# brick_serial_ble.net
KiCad netlist of a schematic drawn in EAGLE
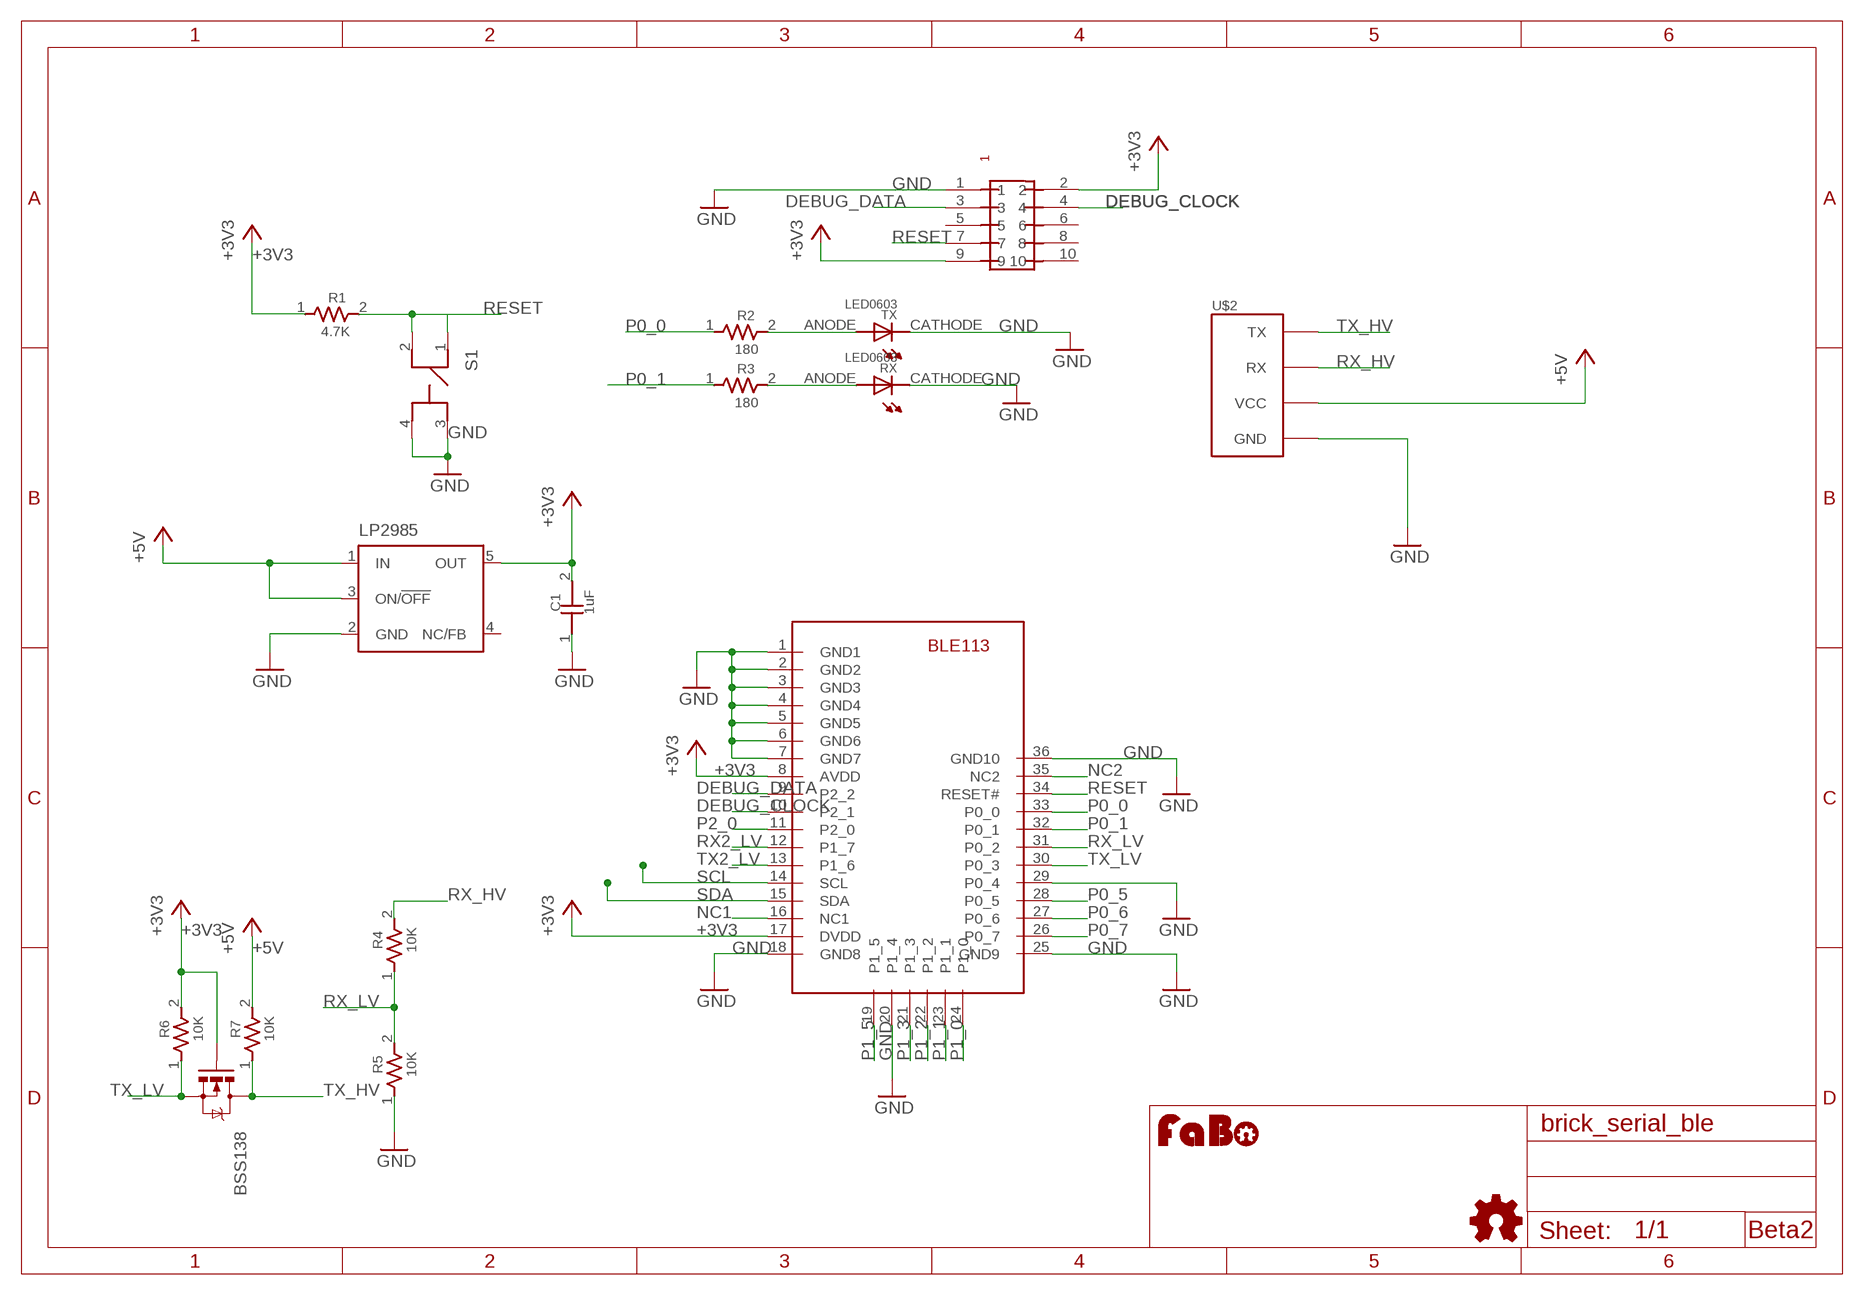
[diagram p0: schematic, sheet 1]

(export (version "E")
  (design (tool "Eeschema 10.0.6"))
  (components
    (comp (ref "BSS138")
      (value "MOSFET-NCHANNELSMD")
      (footprint "eagle-import:SOT23-3")
      (libsource (lib "eagle-import") (part "MOSFET-NCHANNELSMD"))
    )
    (comp (ref "C1")
      (value "1uF")
      (footprint "eagle-import:0603")
      (libsource (lib "eagle-import") (part "CAPACITOR0603"))
    )
    (comp (ref "LP2985")
      (value "LP2985-XXDBVR33")
      (footprint "eagle-import:SOT23-DBV")
      (libsource (lib "eagle-import") (part "LP2985-XXDBVR33"))
    )
    (comp (ref "R1")
      (value "4.7K")
      (footprint "eagle-import:0603")
      (libsource (lib "eagle-import") (part "RESISTOR0603"))
    )
    (comp (ref "R2")
      (value "180")
      (footprint "eagle-import:0603")
      (libsource (lib "eagle-import") (part "RESISTOR0603"))
    )
    (comp (ref "R3")
      (value "180")
      (footprint "eagle-import:0603")
      (libsource (lib "eagle-import") (part "RESISTOR0603"))
    )
    (comp (ref "R4")
      (value "10K")
      (footprint "eagle-import:0603")
      (libsource (lib "eagle-import") (part "RESISTOR0603"))
    )
    (comp (ref "R5")
      (value "10K")
      (footprint "eagle-import:0603")
      (libsource (lib "eagle-import") (part "RESISTOR0603"))
    )
    (comp (ref "R6")
      (value "10K")
      (footprint "eagle-import:0603")
      (libsource (lib "eagle-import") (part "RESISTOR0603"))
    )
    (comp (ref "R7")
      (value "10K")
      (footprint "eagle-import:0603")
      (libsource (lib "eagle-import") (part "RESISTOR0603"))
    )
    (comp (ref "RX")
      (value "LED0603")
      (footprint "eagle-import:0603")
      (libsource (lib "eagle-import") (part "LED0603"))
    )
    (comp (ref "S1")
      (value "SWITCH-LS6J2M-T")
      (footprint "eagle-import:SWITCH-LS6J2M-T")
      (libsource (lib "eagle-import") (part "SWITCH-LS6J2M-T"))
    )
    (comp (ref "TX")
      (value "LED0603")
      (footprint "eagle-import:0603")
      (libsource (lib "eagle-import") (part "LED0603"))
    )
    (comp (ref "U$1")
      (value "PIN-HEADER-SMT(1.27MM)2X5")
      (footprint "eagle-import:PIN-HEADER-SMT(1.27MM)2X5")
      (libsource (lib "eagle-import") (part "PIN-HEADER-SMT(1.27MM)2X5"))
    )
    (comp (ref "U$2")
      (value "BRICK_SERIAL")
      (footprint "eagle-import:BRICK_SERIAL")
      (libsource (lib "eagle-import") (part "BRICK_SERIAL"))
    )
    (comp (ref "U$3")
      (value "LOGO_FABO-S")
      (footprint "eagle-import:LOGO_FABO_S")
      (libsource (lib "eagle-import") (part "LOGO_FABO-S"))
    )
    (comp (ref "U$4")
      (value "LOGO_OSHW-S")
      (footprint "eagle-import:LOGO_OSHW_S")
      (libsource (lib "eagle-import") (part "LOGO_OSHW-S"))
    )
    (comp (ref "U$6")
      (value "BLUEGIGA-BLE113")
      (footprint "eagle-import:BLUEGIGA-BLE113")
      (libsource (lib "eagle-import") (part "BLUEGIGA-BLE113"))
    )
  )
  (nets
    (net (code "1") (name "+3V3") (class "Default")
      (node (ref "BSS138") (pin "1") (pinfunction "G_1") (pintype "passive"))
      (node (ref "C1") (pin "2") (pinfunction "2_2") (pintype "passive"))
      (node (ref "LP2985") (pin "5") (pinfunction "OUT_5") (pintype "passive"))
      (node (ref "R1") (pin "1") (pinfunction "1_1") (pintype "passive"))
      (node (ref "R6") (pin "2") (pinfunction "2_2") (pintype "passive"))
      (node (ref "U$1") (pin "2") (pinfunction "2_2") (pintype "bidirectional"))
      (node (ref "U$1") (pin "9") (pinfunction "9_9") (pintype "bidirectional"))
      (node (ref "U$6") (pin "17") (pinfunction "DVDD_17") (pintype "bidirectional"))
      (node (ref "U$6") (pin "8") (pinfunction "AVDD_8") (pintype "bidirectional"))
    )
    (net (code "2") (name "+5V") (class "Default")
      (node (ref "LP2985") (pin "1") (pinfunction "IN_1") (pintype "input"))
      (node (ref "LP2985") (pin "3") (pinfunction "ON/~{OFF}_3") (pintype "input"))
      (node (ref "R7") (pin "2") (pinfunction "2_2") (pintype "passive"))
      (node (ref "U$2") (pin "VCC") (pinfunction "VCC_VCC") (pintype "bidirectional"))
    )
    (net (code "3") (name "/DEBUG_CLOCK") (class "Default")
      (node (ref "U$1") (pin "4") (pinfunction "4_4") (pintype "bidirectional"))
      (node (ref "U$6") (pin "10") (pinfunction "P2_1_10") (pintype "bidirectional"))
    )
    (net (code "4") (name "/DEBUG_DATA") (class "Default")
      (node (ref "U$1") (pin "3") (pinfunction "3_3") (pintype "bidirectional"))
      (node (ref "U$6") (pin "9") (pinfunction "P2_2_9") (pintype "bidirectional"))
    )
    (net (code "5") (name "/NC1") (class "Default")
      (node (ref "U$6") (pin "16") (pinfunction "NC1_16") (pintype "bidirectional"))
    )
    (net (code "6") (name "/NC2") (class "Default")
      (node (ref "U$6") (pin "35") (pinfunction "NC2_35") (pintype "bidirectional"))
    )
    (net (code "7") (name "/P0_0") (class "Default")
      (node (ref "R2") (pin "1") (pinfunction "1_1") (pintype "passive"))
      (node (ref "U$6") (pin "33") (pinfunction "P0_0_33") (pintype "bidirectional"))
    )
    (net (code "8") (name "/P0_1") (class "Default")
      (node (ref "R3") (pin "1") (pinfunction "1_1") (pintype "passive"))
      (node (ref "U$6") (pin "32") (pinfunction "P0_1_32") (pintype "bidirectional"))
    )
    (net (code "9") (name "/P0_5") (class "Default")
      (node (ref "U$6") (pin "28") (pinfunction "P0_5_28") (pintype "bidirectional"))
    )
    (net (code "10") (name "/P0_6") (class "Default")
      (node (ref "U$6") (pin "27") (pinfunction "P0_6_27") (pintype "bidirectional"))
    )
    (net (code "11") (name "/P0_7") (class "Default")
      (node (ref "U$6") (pin "26") (pinfunction "P0_7_26") (pintype "bidirectional"))
    )
    (net (code "12") (name "/P1_0") (class "Default")
      (node (ref "U$6") (pin "24") (pinfunction "P1_0_24") (pintype "bidirectional"))
    )
    (net (code "13") (name "/P1_1") (class "Default")
      (node (ref "U$6") (pin "23") (pinfunction "P1_1_23") (pintype "bidirectional"))
    )
    (net (code "14") (name "/P1_2") (class "Default")
      (node (ref "U$6") (pin "22") (pinfunction "P1_2_22") (pintype "bidirectional"))
    )
    (net (code "15") (name "/P1_3") (class "Default")
      (node (ref "U$6") (pin "21") (pinfunction "P1_3_21") (pintype "bidirectional"))
    )
    (net (code "16") (name "/P1_5") (class "Default")
      (node (ref "U$6") (pin "19") (pinfunction "P1_5_19") (pintype "bidirectional"))
    )
    (net (code "17") (name "/P2_0") (class "Default")
      (node (ref "U$6") (pin "11") (pinfunction "P2_0_11") (pintype "bidirectional"))
    )
    (net (code "18") (name "/RESET") (class "Default")
      (node (ref "R1") (pin "2") (pinfunction "2_2") (pintype "passive"))
      (node (ref "S1") (pin "1") (pinfunction "1_1") (pintype "bidirectional"))
      (node (ref "S1") (pin "2") (pinfunction "2_2") (pintype "bidirectional"))
      (node (ref "U$1") (pin "7") (pinfunction "7_7") (pintype "bidirectional"))
      (node (ref "U$6") (pin "34") (pinfunction "RESET#_34") (pintype "bidirectional"))
    )
    (net (code "19") (name "/RX2_LV") (class "Default")
      (node (ref "U$6") (pin "12") (pinfunction "P1_7_12") (pintype "bidirectional"))
    )
    (net (code "20") (name "/RX_HV") (class "Default")
      (node (ref "R4") (pin "2") (pinfunction "2_2") (pintype "passive"))
      (node (ref "U$2") (pin "RX") (pinfunction "RX_RX") (pintype "bidirectional"))
    )
    (net (code "21") (name "/RX_LV") (class "Default")
      (node (ref "R4") (pin "1") (pinfunction "1_1") (pintype "passive"))
      (node (ref "R5") (pin "2") (pinfunction "2_2") (pintype "passive"))
      (node (ref "U$6") (pin "31") (pinfunction "P0_2_31") (pintype "bidirectional"))
    )
    (net (code "22") (name "/SCL") (class "Default")
      (node (ref "U$6") (pin "14") (pinfunction "SCL_14") (pintype "bidirectional"))
    )
    (net (code "23") (name "/SDA") (class "Default")
      (node (ref "U$6") (pin "15") (pinfunction "SDA_15") (pintype "bidirectional"))
    )
    (net (code "24") (name "/TX2_LV") (class "Default")
      (node (ref "U$6") (pin "13") (pinfunction "P1_6_13") (pintype "bidirectional"))
    )
    (net (code "25") (name "/TX_HV") (class "Default")
      (node (ref "BSS138") (pin "3") (pinfunction "D_3") (pintype "passive"))
      (node (ref "R7") (pin "1") (pinfunction "1_1") (pintype "passive"))
      (node (ref "U$2") (pin "TX") (pinfunction "TX_TX") (pintype "bidirectional"))
    )
    (net (code "26") (name "/TX_LV") (class "Default")
      (node (ref "BSS138") (pin "2") (pinfunction "S_2") (pintype "passive"))
      (node (ref "R6") (pin "1") (pinfunction "1_1") (pintype "passive"))
      (node (ref "U$6") (pin "30") (pinfunction "P0_3_30") (pintype "bidirectional"))
    )
    (net (code "27") (name "GND") (class "Default")
      (node (ref "C1") (pin "1") (pinfunction "1_1") (pintype "passive"))
      (node (ref "LP2985") (pin "2") (pinfunction "GND_2") (pintype "power_in"))
      (node (ref "R5") (pin "1") (pinfunction "1_1") (pintype "passive"))
      (node (ref "RX") (pin "CATHODE") (pinfunction "CATHODE_CATHODE") (pintype "passive"))
      (node (ref "S1") (pin "3") (pinfunction "3_3") (pintype "bidirectional"))
      (node (ref "S1") (pin "4") (pinfunction "4_4") (pintype "bidirectional"))
      (node (ref "TX") (pin "CATHODE") (pinfunction "CATHODE_CATHODE") (pintype "passive"))
      (node (ref "U$1") (pin "1") (pinfunction "1_1") (pintype "bidirectional"))
      (node (ref "U$2") (pin "GND") (pinfunction "GND_GND") (pintype "bidirectional"))
      (node (ref "U$6") (pin "1") (pinfunction "GND1_1") (pintype "bidirectional"))
      (node (ref "U$6") (pin "18") (pinfunction "GND8_18") (pintype "bidirectional"))
      (node (ref "U$6") (pin "2") (pinfunction "GND2_2") (pintype "bidirectional"))
      (node (ref "U$6") (pin "20") (pinfunction "P1_4_20") (pintype "bidirectional"))
      (node (ref "U$6") (pin "25") (pinfunction "GND9_25") (pintype "bidirectional"))
      (node (ref "U$6") (pin "29") (pinfunction "P0_4_29") (pintype "bidirectional"))
      (node (ref "U$6") (pin "3") (pinfunction "GND3_3") (pintype "bidirectional"))
      (node (ref "U$6") (pin "36") (pinfunction "GND10_36") (pintype "bidirectional"))
      (node (ref "U$6") (pin "4") (pinfunction "GND4_4") (pintype "bidirectional"))
      (node (ref "U$6") (pin "5") (pinfunction "GND5_5") (pintype "bidirectional"))
      (node (ref "U$6") (pin "6") (pinfunction "GND6_6") (pintype "bidirectional"))
      (node (ref "U$6") (pin "7") (pinfunction "GND7_7") (pintype "bidirectional"))
    )
    (net (code "28") (name "Net-(R2-Pad2)") (class "Default")
      (node (ref "R2") (pin "2") (pinfunction "2_2") (pintype "passive"))
      (node (ref "TX") (pin "ANODE") (pinfunction "ANODE_ANODE") (pintype "passive"))
    )
    (net (code "29") (name "Net-(R3-Pad2)") (class "Default")
      (node (ref "R3") (pin "2") (pinfunction "2_2") (pintype "passive"))
      (node (ref "RX") (pin "ANODE") (pinfunction "ANODE_ANODE") (pintype "passive"))
    )
    (net (code "30") (name "unconnected-(LP2985-NC{slash}FB-Pad4)") (class "Default")
      (node (ref "LP2985") (pin "4") (pinfunction "NC/FB_4") (pintype "passive"))
    )
    (net (code "31") (name "unconnected-(U$1-Pad5)") (class "Default")
      (node (ref "U$1") (pin "5") (pinfunction "5_5") (pintype "bidirectional"))
    )
    (net (code "32") (name "unconnected-(U$1-Pad6)") (class "Default")
      (node (ref "U$1") (pin "6") (pinfunction "6_6") (pintype "bidirectional"))
    )
    (net (code "33") (name "unconnected-(U$1-Pad8)") (class "Default")
      (node (ref "U$1") (pin "8") (pinfunction "8_8") (pintype "bidirectional"))
    )
    (net (code "34") (name "unconnected-(U$1-Pad10)") (class "Default")
      (node (ref "U$1") (pin "10") (pinfunction "10_10") (pintype "bidirectional"))
    )
  )
)
